# rs-485-multiplier-v2-9.net
KiCad netlist of a schematic drawn in EAGLE
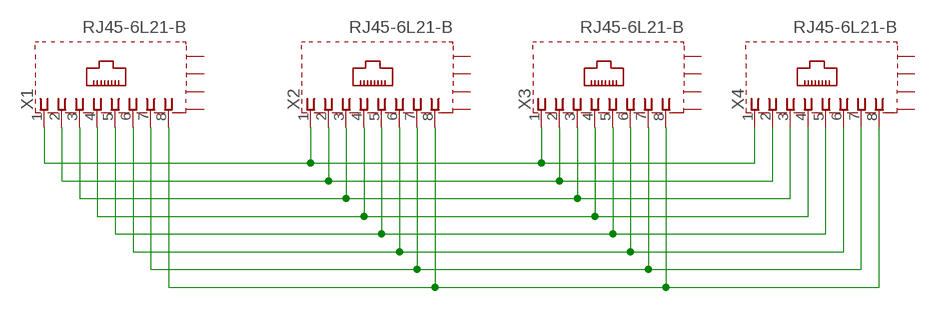
[diagram p0: schematic, sheet 1]

(export (version "E")
  (design (tool "Eeschema 10.0.6"))
  (components
    (comp (ref "X1")
      (value "RJ45-6L21-B")
      (footprint "eagle-import:RJ45-SHIELD1")
      (libsource (lib "eagle-import") (part "RJ4521-B-6L"))
    )
    (comp (ref "X2")
      (value "RJ45-6L21-B")
      (footprint "eagle-import:RJ45-SHIELD1")
      (libsource (lib "eagle-import") (part "RJ4521-B-6L"))
    )
    (comp (ref "X3")
      (value "RJ45-6L21-B")
      (footprint "eagle-import:RJ45-SHIELD1")
      (libsource (lib "eagle-import") (part "RJ4521-B-6L"))
    )
    (comp (ref "X4")
      (value "RJ45-6L21-B")
      (footprint "eagle-import:RJ45-SHIELD1")
      (libsource (lib "eagle-import") (part "RJ4521-B-6L"))
    )
  )
  (nets
    (net (code "1") (name "Net-(X1-Pad1)") (class "Default")
      (node (ref "X1") (pin "1") (pinfunction "1_1") (pintype "passive"))
      (node (ref "X2") (pin "1") (pinfunction "1_1") (pintype "passive"))
      (node (ref "X3") (pin "1") (pinfunction "1_1") (pintype "passive"))
      (node (ref "X4") (pin "1") (pinfunction "1_1") (pintype "passive"))
    )
    (net (code "2") (name "Net-(X1-Pad2)") (class "Default")
      (node (ref "X1") (pin "2") (pinfunction "2_2") (pintype "passive"))
      (node (ref "X2") (pin "2") (pinfunction "2_2") (pintype "passive"))
      (node (ref "X3") (pin "2") (pinfunction "2_2") (pintype "passive"))
      (node (ref "X4") (pin "2") (pinfunction "2_2") (pintype "passive"))
    )
    (net (code "3") (name "Net-(X1-Pad3)") (class "Default")
      (node (ref "X1") (pin "3") (pinfunction "3_3") (pintype "passive"))
      (node (ref "X2") (pin "3") (pinfunction "3_3") (pintype "passive"))
      (node (ref "X3") (pin "3") (pinfunction "3_3") (pintype "passive"))
      (node (ref "X4") (pin "3") (pinfunction "3_3") (pintype "passive"))
    )
    (net (code "4") (name "Net-(X1-Pad4)") (class "Default")
      (node (ref "X1") (pin "4") (pinfunction "4_4") (pintype "passive"))
      (node (ref "X2") (pin "4") (pinfunction "4_4") (pintype "passive"))
      (node (ref "X3") (pin "4") (pinfunction "4_4") (pintype "passive"))
      (node (ref "X4") (pin "4") (pinfunction "4_4") (pintype "passive"))
    )
    (net (code "5") (name "Net-(X1-Pad5)") (class "Default")
      (node (ref "X1") (pin "5") (pinfunction "5_5") (pintype "passive"))
      (node (ref "X2") (pin "5") (pinfunction "5_5") (pintype "passive"))
      (node (ref "X3") (pin "5") (pinfunction "5_5") (pintype "passive"))
      (node (ref "X4") (pin "5") (pinfunction "5_5") (pintype "passive"))
    )
    (net (code "6") (name "Net-(X1-Pad6)") (class "Default")
      (node (ref "X1") (pin "6") (pinfunction "6_6") (pintype "passive"))
      (node (ref "X2") (pin "6") (pinfunction "6_6") (pintype "passive"))
      (node (ref "X3") (pin "6") (pinfunction "6_6") (pintype "passive"))
      (node (ref "X4") (pin "6") (pinfunction "6_6") (pintype "passive"))
    )
    (net (code "7") (name "Net-(X1-Pad7)") (class "Default")
      (node (ref "X1") (pin "7") (pinfunction "7_7") (pintype "passive"))
      (node (ref "X2") (pin "7") (pinfunction "7_7") (pintype "passive"))
      (node (ref "X3") (pin "7") (pinfunction "7_7") (pintype "passive"))
      (node (ref "X4") (pin "7") (pinfunction "7_7") (pintype "passive"))
    )
    (net (code "8") (name "Net-(X1-Pad8)") (class "Default")
      (node (ref "X1") (pin "8") (pinfunction "8_8") (pintype "passive"))
      (node (ref "X2") (pin "8") (pinfunction "8_8") (pintype "passive"))
      (node (ref "X3") (pin "8") (pinfunction "8_8") (pintype "passive"))
      (node (ref "X4") (pin "8") (pinfunction "8_8") (pintype "passive"))
    )
    (net (code "9") (name "unconnected-(X1-S-PadS1)") (class "Default")
      (node (ref "X1") (pin "S1") (pinfunction "S_S1") (pintype "passive"))
    )
    (net (code "10") (name "unconnected-(X1-S-PadS2)") (class "Default")
      (node (ref "X1") (pin "S2") (pinfunction "S_S2") (pintype "passive"))
    )
    (net (code "11") (name "unconnected-(X1-S-PadS3)") (class "Default")
      (node (ref "X1") (pin "S3") (pinfunction "S_S3") (pintype "passive"))
    )
    (net (code "12") (name "unconnected-(X1-S-PadS4)") (class "Default")
      (node (ref "X1") (pin "S4") (pinfunction "S_S4") (pintype "passive"))
    )
    (net (code "13") (name "unconnected-(X2-S-PadS1)") (class "Default")
      (node (ref "X2") (pin "S1") (pinfunction "S_S1") (pintype "passive"))
    )
    (net (code "14") (name "unconnected-(X2-S-PadS2)") (class "Default")
      (node (ref "X2") (pin "S2") (pinfunction "S_S2") (pintype "passive"))
    )
    (net (code "15") (name "unconnected-(X2-S-PadS3)") (class "Default")
      (node (ref "X2") (pin "S3") (pinfunction "S_S3") (pintype "passive"))
    )
    (net (code "16") (name "unconnected-(X2-S-PadS4)") (class "Default")
      (node (ref "X2") (pin "S4") (pinfunction "S_S4") (pintype "passive"))
    )
    (net (code "17") (name "unconnected-(X3-S-PadS1)") (class "Default")
      (node (ref "X3") (pin "S1") (pinfunction "S_S1") (pintype "passive"))
    )
    (net (code "18") (name "unconnected-(X3-S-PadS2)") (class "Default")
      (node (ref "X3") (pin "S2") (pinfunction "S_S2") (pintype "passive"))
    )
    (net (code "19") (name "unconnected-(X3-S-PadS3)") (class "Default")
      (node (ref "X3") (pin "S3") (pinfunction "S_S3") (pintype "passive"))
    )
    (net (code "20") (name "unconnected-(X3-S-PadS4)") (class "Default")
      (node (ref "X3") (pin "S4") (pinfunction "S_S4") (pintype "passive"))
    )
    (net (code "21") (name "unconnected-(X4-S-PadS1)") (class "Default")
      (node (ref "X4") (pin "S1") (pinfunction "S_S1") (pintype "passive"))
    )
    (net (code "22") (name "unconnected-(X4-S-PadS2)") (class "Default")
      (node (ref "X4") (pin "S2") (pinfunction "S_S2") (pintype "passive"))
    )
    (net (code "23") (name "unconnected-(X4-S-PadS3)") (class "Default")
      (node (ref "X4") (pin "S3") (pinfunction "S_S3") (pintype "passive"))
    )
    (net (code "24") (name "unconnected-(X4-S-PadS4)") (class "Default")
      (node (ref "X4") (pin "S4") (pinfunction "S_S4") (pintype "passive"))
    )
  )
)
